# airttenuator.net
KiCad netlist of a schematic drawn in EAGLE
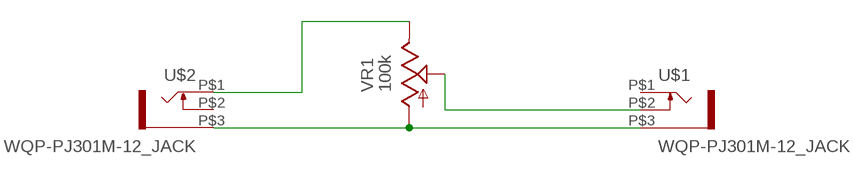
[diagram p0: schematic, sheet 1]

(export (version "E")
  (design (tool "Eeschema 10.0.6"))
  (components
    (comp (ref "U$1")
      (value "WQP-PJ301M-12_JACK")
      (footprint "eagle-import:WQP-PJ301M-12_JACK")
      (libsource (lib "eagle-import") (part "WQP-PJ301M-12_JACK"))
    )
    (comp (ref "U$2")
      (value "WQP-PJ301M-12_JACK")
      (footprint "eagle-import:WQP-PJ301M-12_JACK")
      (libsource (lib "eagle-import") (part "WQP-PJ301M-12_JACK"))
    )
    (comp (ref "VR1")
      (value "100k")
      (footprint "eagle-import:9MM_SNAP-IN_POT")
      (libsource (lib "eagle-import") (part "9MM_SNAP-IN_POT_"))
    )
  )
  (nets
    (net (code "1") (name "Net-(U$1-1)") (class "Default")
      (node (ref "U$1") (pin "P$3") (pinfunction "1_P$3") (pintype "passive"))
      (node (ref "U$2") (pin "P$3") (pinfunction "1_P$3") (pintype "passive"))
      (node (ref "VR1") (pin "1") (pinfunction "A_1") (pintype "passive"))
    )
    (net (code "2") (name "Net-(U$1-3)") (class "Default")
      (node (ref "U$1") (pin "P$2") (pinfunction "3_P$2") (pintype "passive"))
      (node (ref "VR1") (pin "2") (pinfunction "S_2") (pintype "passive"))
    )
    (net (code "3") (name "Net-(U$2-2)") (class "Default")
      (node (ref "U$2") (pin "P$1") (pinfunction "2_P$1") (pintype "passive"))
      (node (ref "VR1") (pin "3") (pinfunction "E_3") (pintype "passive"))
    )
    (net (code "4") (name "unconnected-(U$1-2-PadP$1)") (class "Default")
      (node (ref "U$1") (pin "P$1") (pinfunction "2_P$1") (pintype "passive"))
    )
    (net (code "5") (name "unconnected-(U$2-3-PadP$2)") (class "Default")
      (node (ref "U$2") (pin "P$2") (pinfunction "3_P$2") (pintype "passive"))
    )
  )
)
